# xhfc-breakout.net
KiCad netlist of a schematic drawn in EAGLE
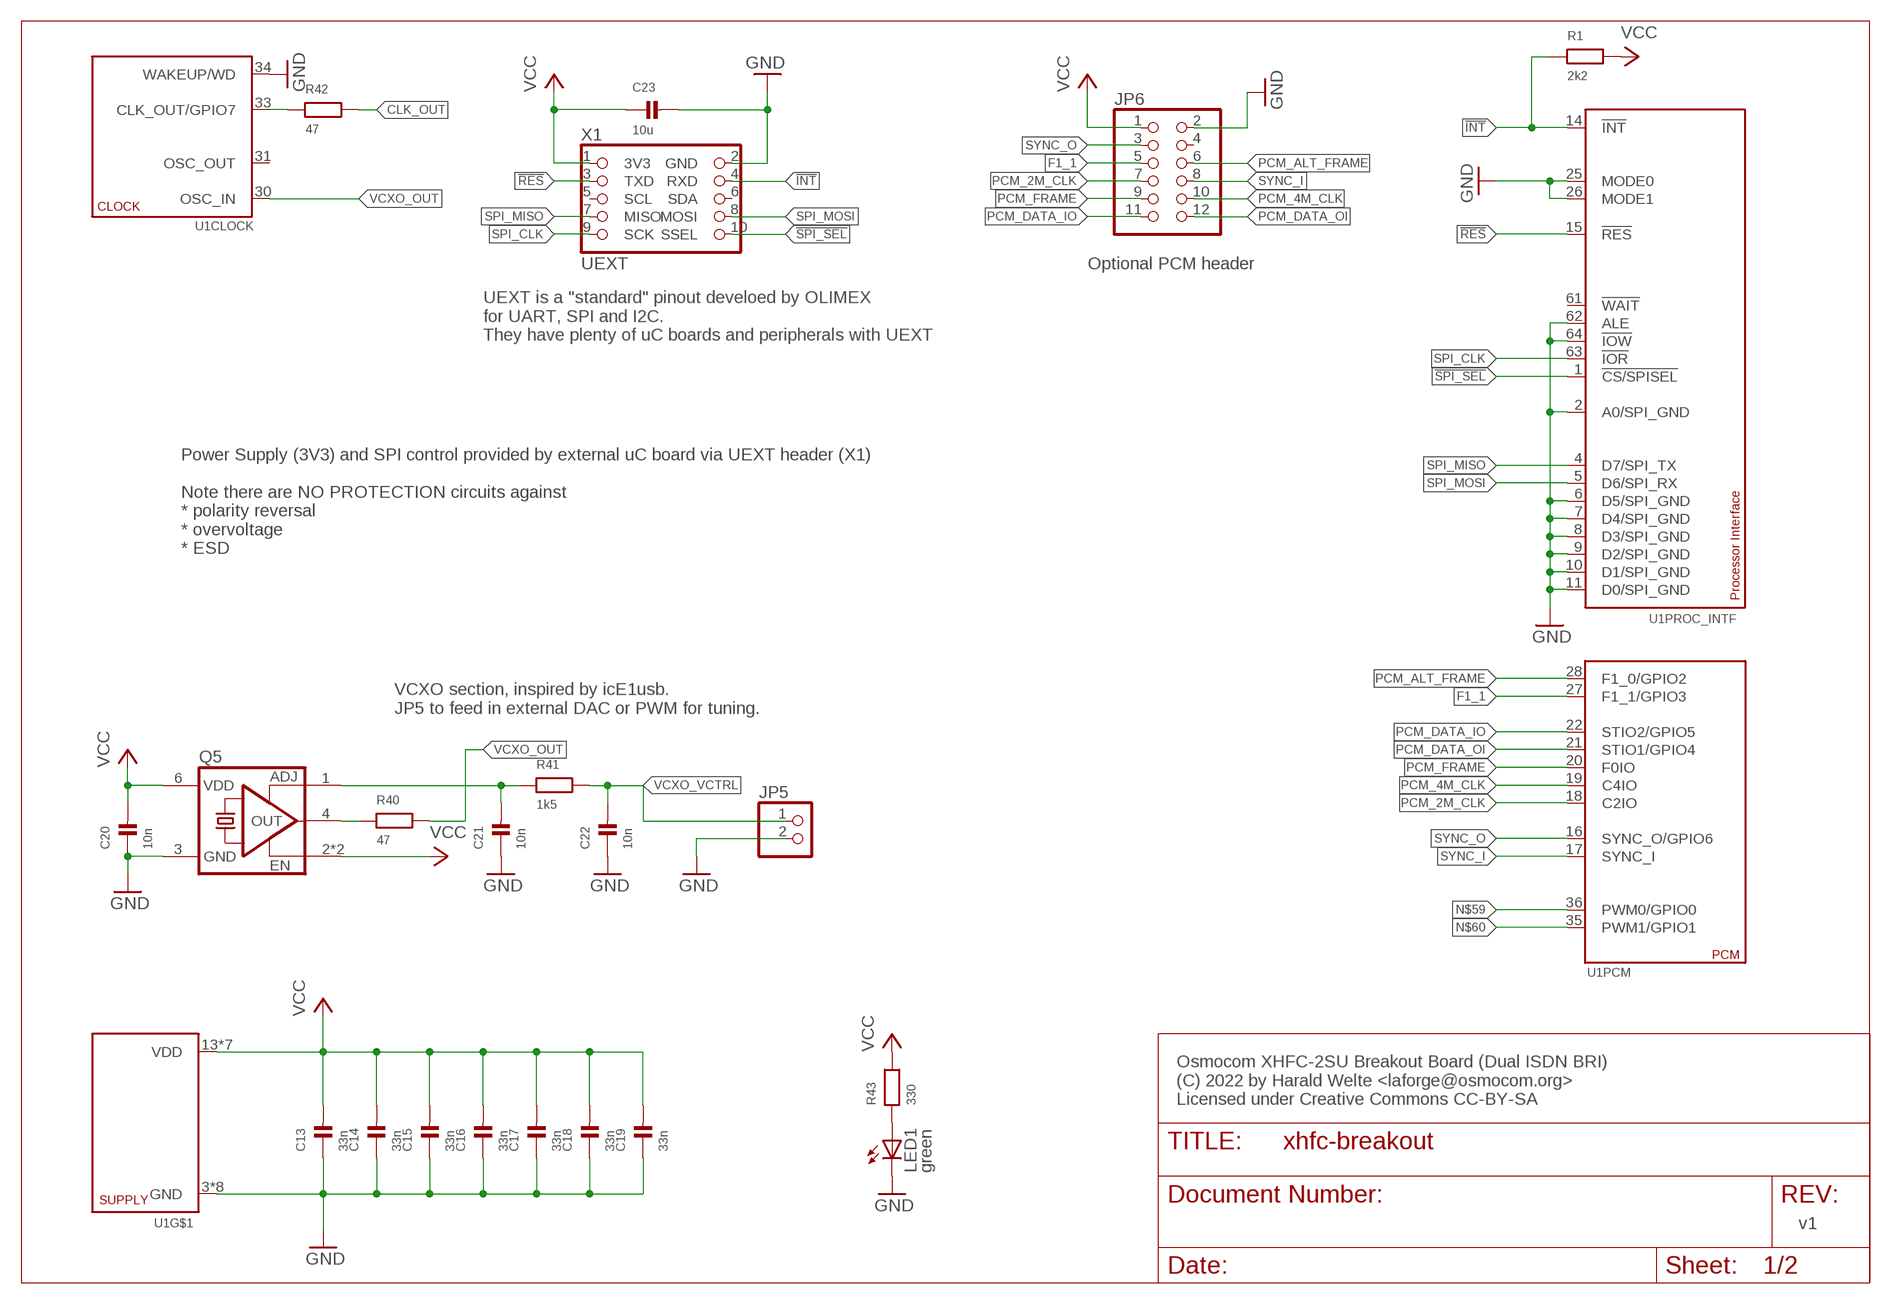
[diagram p0: schematic, sheet 1]
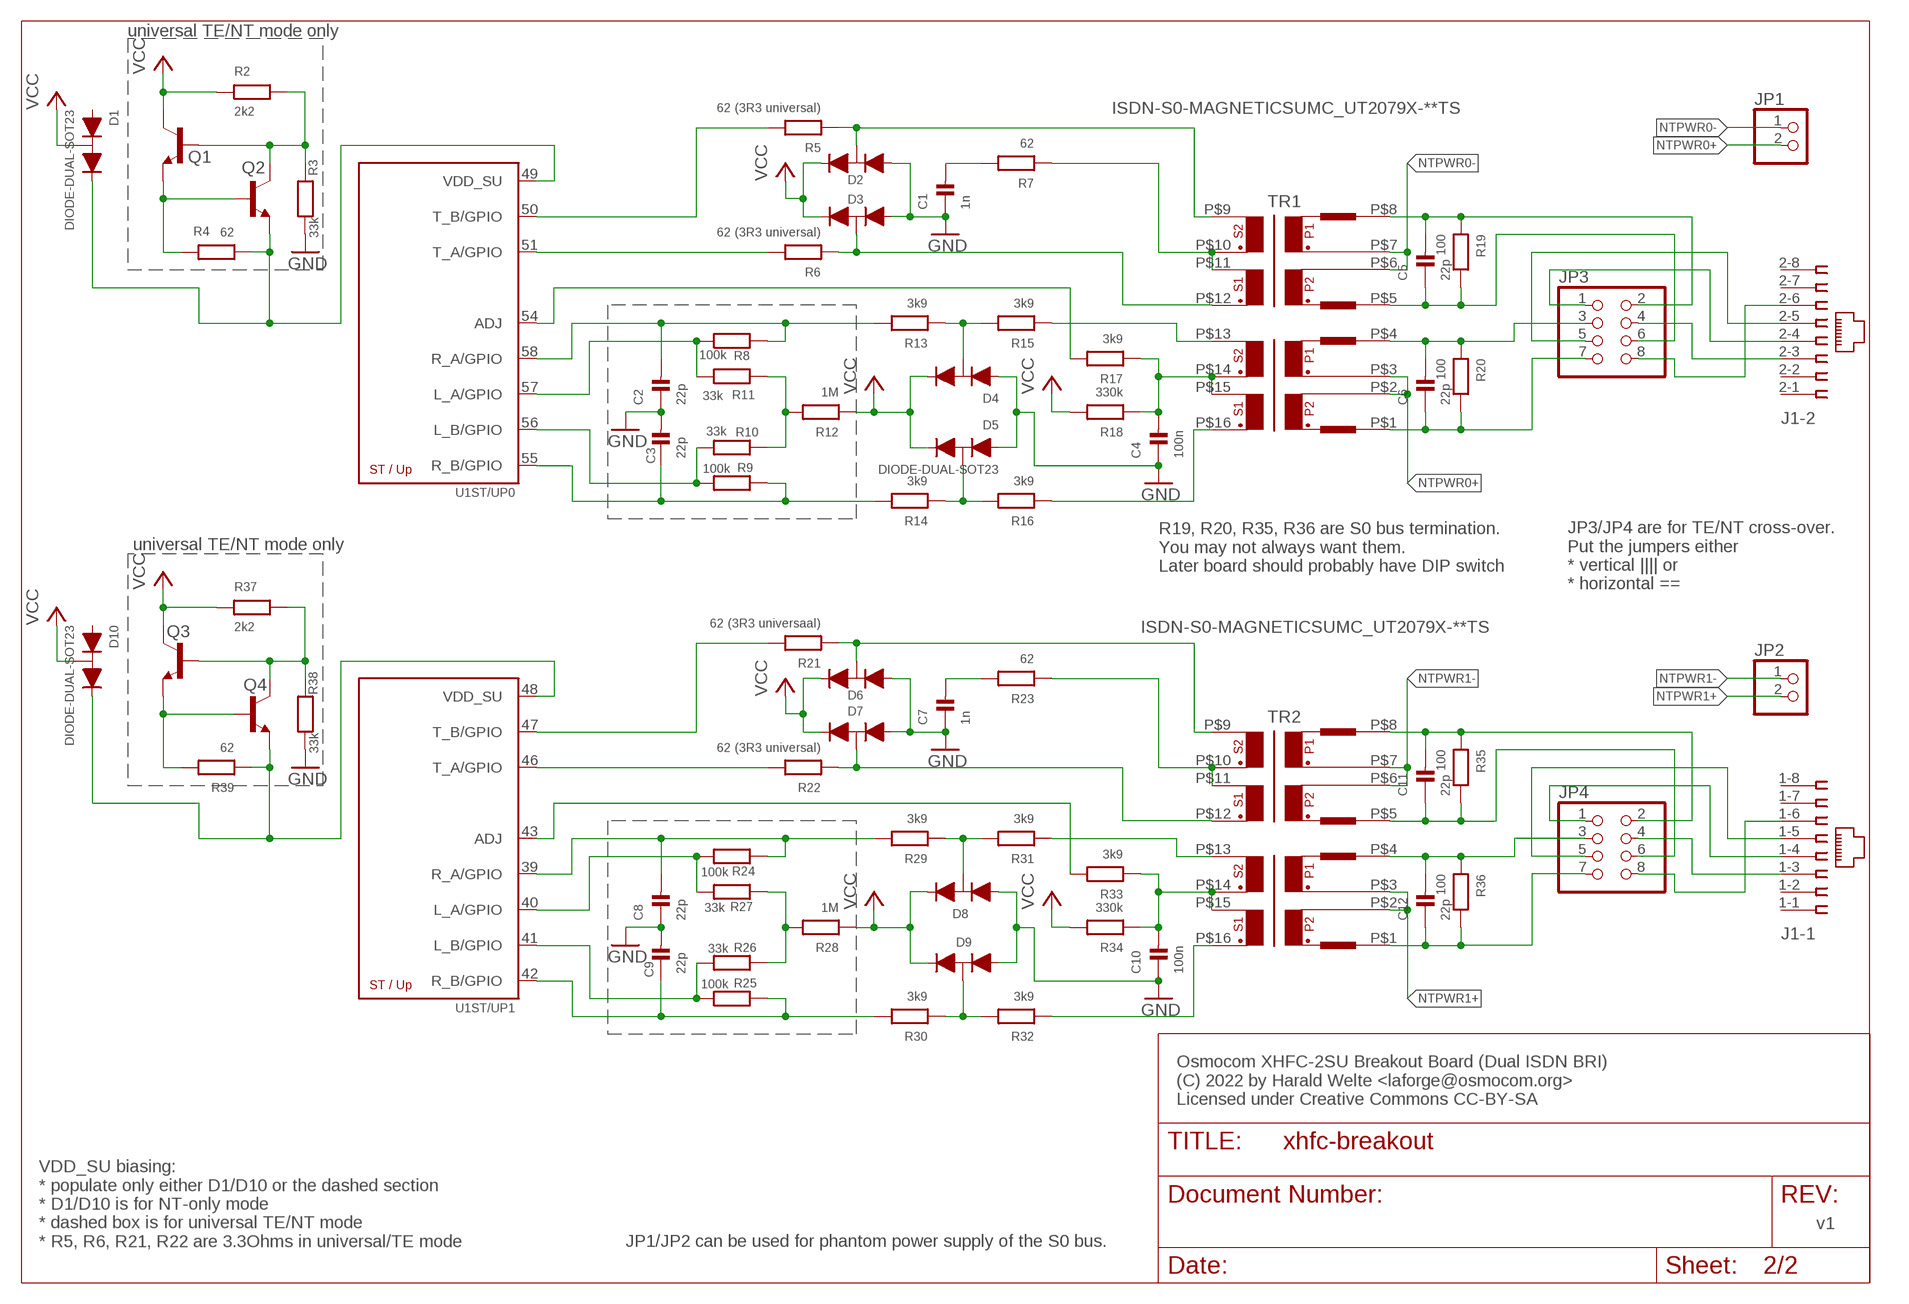
[diagram p1: schematic, sheet 2]

(export (version "E")
  (design (tool "Eeschema 10.0.6"))
  (components
    (comp (ref "C1")
      (value "1n")
      (footprint "eagle-import:_0603")
      (description "NO DESCRIPTION")
      (fields
        (field (name "MANUFACTURER") "UNKNOWN MANUFACTURER")
        (field (name "MANUFACTURERPARTNUMBER") "UNKNOWN MANUFACTURER PART NUMBER")
      )
      (libsource (lib "eagle-import") (part "CAP_CERAMIC_0603"))
    )
    (comp (ref "C2")
      (value "22p")
      (footprint "eagle-import:_0603")
      (description "NO DESCRIPTION")
      (fields
        (field (name "MANUFACTURER") "UNKNOWN MANUFACTURER")
        (field (name "MANUFACTURERPARTNUMBER") "UNKNOWN MANUFACTURER PART NUMBER")
      )
      (libsource (lib "eagle-import") (part "CAP_CERAMIC_0603"))
    )
    (comp (ref "C3")
      (value "22p")
      (footprint "eagle-import:_0603")
      (description "NO DESCRIPTION")
      (fields
        (field (name "MANUFACTURER") "UNKNOWN MANUFACTURER")
        (field (name "MANUFACTURERPARTNUMBER") "UNKNOWN MANUFACTURER PART NUMBER")
      )
      (libsource (lib "eagle-import") (part "CAP_CERAMIC_0603"))
    )
    (comp (ref "C4")
      (value "100n")
      (footprint "eagle-import:_0603")
      (description "NO DESCRIPTION")
      (fields
        (field (name "MANUFACTURER") "UNKNOWN MANUFACTURER")
        (field (name "MANUFACTURERPARTNUMBER") "UNKNOWN MANUFACTURER PART NUMBER")
      )
      (libsource (lib "eagle-import") (part "CAP_CERAMIC_0603"))
    )
    (comp (ref "C5")
      (value "22p")
      (footprint "eagle-import:_0603")
      (description "NO DESCRIPTION")
      (fields
        (field (name "MANUFACTURER") "UNKNOWN MANUFACTURER")
        (field (name "MANUFACTURERPARTNUMBER") "UNKNOWN MANUFACTURER PART NUMBER")
      )
      (libsource (lib "eagle-import") (part "CAP_CERAMIC_0603"))
    )
    (comp (ref "C6")
      (value "22p")
      (footprint "eagle-import:_0603")
      (description "NO DESCRIPTION")
      (fields
        (field (name "MANUFACTURER") "UNKNOWN MANUFACTURER")
        (field (name "MANUFACTURERPARTNUMBER") "UNKNOWN MANUFACTURER PART NUMBER")
      )
      (libsource (lib "eagle-import") (part "CAP_CERAMIC_0603"))
    )
    (comp (ref "C7")
      (value "1n")
      (footprint "eagle-import:_0603")
      (description "NO DESCRIPTION")
      (fields
        (field (name "MANUFACTURER") "UNKNOWN MANUFACTURER")
        (field (name "MANUFACTURERPARTNUMBER") "UNKNOWN MANUFACTURER PART NUMBER")
      )
      (libsource (lib "eagle-import") (part "CAP_CERAMIC_0603"))
    )
    (comp (ref "C8")
      (value "22p")
      (footprint "eagle-import:_0603")
      (description "NO DESCRIPTION")
      (fields
        (field (name "MANUFACTURER") "UNKNOWN MANUFACTURER")
        (field (name "MANUFACTURERPARTNUMBER") "UNKNOWN MANUFACTURER PART NUMBER")
      )
      (libsource (lib "eagle-import") (part "CAP_CERAMIC_0603"))
    )
    (comp (ref "C9")
      (value "22p")
      (footprint "eagle-import:_0603")
      (description "NO DESCRIPTION")
      (fields
        (field (name "MANUFACTURER") "UNKNOWN MANUFACTURER")
        (field (name "MANUFACTURERPARTNUMBER") "UNKNOWN MANUFACTURER PART NUMBER")
      )
      (libsource (lib "eagle-import") (part "CAP_CERAMIC_0603"))
    )
    (comp (ref "C10")
      (value "100n")
      (footprint "eagle-import:_0603")
      (description "NO DESCRIPTION")
      (fields
        (field (name "MANUFACTURER") "UNKNOWN MANUFACTURER")
        (field (name "MANUFACTURERPARTNUMBER") "UNKNOWN MANUFACTURER PART NUMBER")
      )
      (libsource (lib "eagle-import") (part "CAP_CERAMIC_0603"))
    )
    (comp (ref "C11")
      (value "22p")
      (footprint "eagle-import:_0603")
      (description "NO DESCRIPTION")
      (fields
        (field (name "MANUFACTURER") "UNKNOWN MANUFACTURER")
        (field (name "MANUFACTURERPARTNUMBER") "UNKNOWN MANUFACTURER PART NUMBER")
      )
      (libsource (lib "eagle-import") (part "CAP_CERAMIC_0603"))
    )
    (comp (ref "C12")
      (value "22p")
      (footprint "eagle-import:_0603")
      (description "NO DESCRIPTION")
      (fields
        (field (name "MANUFACTURER") "UNKNOWN MANUFACTURER")
        (field (name "MANUFACTURERPARTNUMBER") "UNKNOWN MANUFACTURER PART NUMBER")
      )
      (libsource (lib "eagle-import") (part "CAP_CERAMIC_0603"))
    )
    (comp (ref "D1")
      (value "DIODE-DUAL-SOT23")
      (footprint "eagle-import:SOT23-3")
      (description "DIODE ARRAY GP 100V 150MA SOT323")
      (fields
        (field (name "MANUFACTURER") "Nexperia USA Inc.")
        (field (name "MANUFACTURERPARTNUMBER") "BAV99W,115")
      )
      (libsource (lib "eagle-import") (part "DIODE-DUAL-SOT23"))
    )
    (comp (ref "D2")
      (value "DIODE-DUAL-SOT23")
      (footprint "eagle-import:SOT23-3")
      (description "DIODE ARRAY GP 100V 150MA SOT323")
      (fields
        (field (name "MANUFACTURER") "Nexperia USA Inc.")
        (field (name "MANUFACTURERPARTNUMBER") "BAV99W,115")
      )
      (libsource (lib "eagle-import") (part "DIODE-DUAL-SOT23"))
    )
    (comp (ref "D3")
      (value "DIODE-DUAL-SOT23")
      (footprint "eagle-import:SOT23-3")
      (description "DIODE ARRAY GP 100V 150MA SOT323")
      (fields
        (field (name "MANUFACTURER") "Nexperia USA Inc.")
        (field (name "MANUFACTURERPARTNUMBER") "BAV99W,115")
      )
      (libsource (lib "eagle-import") (part "DIODE-DUAL-SOT23"))
    )
    (comp (ref "D4")
      (value "DIODE-DUAL-SOT23")
      (footprint "eagle-import:SOT23-3")
      (description "DIODE ARRAY GP 100V 150MA SOT323")
      (fields
        (field (name "MANUFACTURER") "Nexperia USA Inc.")
        (field (name "MANUFACTURERPARTNUMBER") "BAV99W,115")
      )
      (libsource (lib "eagle-import") (part "DIODE-DUAL-SOT23"))
    )
    (comp (ref "D5")
      (value "DIODE-DUAL-SOT23")
      (footprint "eagle-import:SOT23-3")
      (description "DIODE ARRAY GP 100V 150MA SOT323")
      (fields
        (field (name "MANUFACTURER") "Nexperia USA Inc.")
        (field (name "MANUFACTURERPARTNUMBER") "BAV99W,115")
      )
      (libsource (lib "eagle-import") (part "DIODE-DUAL-SOT23"))
    )
    (comp (ref "D6")
      (value "DIODE-DUAL-SOT23")
      (footprint "eagle-import:SOT23-3")
      (description "DIODE ARRAY GP 100V 150MA SOT323")
      (fields
        (field (name "MANUFACTURER") "Nexperia USA Inc.")
        (field (name "MANUFACTURERPARTNUMBER") "BAV99W,115")
      )
      (libsource (lib "eagle-import") (part "DIODE-DUAL-SOT23"))
    )
    (comp (ref "D7")
      (value "DIODE-DUAL-SOT23")
      (footprint "eagle-import:SOT23-3")
      (description "DIODE ARRAY GP 100V 150MA SOT323")
      (fields
        (field (name "MANUFACTURER") "Nexperia USA Inc.")
        (field (name "MANUFACTURERPARTNUMBER") "BAV99W,115")
      )
      (libsource (lib "eagle-import") (part "DIODE-DUAL-SOT23"))
    )
    (comp (ref "D8")
      (value "DIODE-DUAL-SOT23")
      (footprint "eagle-import:SOT23-3")
      (description "DIODE ARRAY GP 100V 150MA SOT323")
      (fields
        (field (name "MANUFACTURER") "Nexperia USA Inc.")
        (field (name "MANUFACTURERPARTNUMBER") "BAV99W,115")
      )
      (libsource (lib "eagle-import") (part "DIODE-DUAL-SOT23"))
    )
    (comp (ref "D9")
      (value "DIODE-DUAL-SOT23")
      (footprint "eagle-import:SOT23-3")
      (description "DIODE ARRAY GP 100V 150MA SOT323")
      (fields
        (field (name "MANUFACTURER") "Nexperia USA Inc.")
        (field (name "MANUFACTURERPARTNUMBER") "BAV99W,115")
      )
      (libsource (lib "eagle-import") (part "DIODE-DUAL-SOT23"))
    )
    (comp (ref "D10")
      (value "DIODE-DUAL-SOT23")
      (footprint "eagle-import:SOT23-3")
      (description "DIODE ARRAY GP 100V 150MA SOT323")
      (fields
        (field (name "MANUFACTURER") "Nexperia USA Inc.")
        (field (name "MANUFACTURERPARTNUMBER") "BAV99W,115")
      )
      (libsource (lib "eagle-import") (part "DIODE-DUAL-SOT23"))
    )
    (comp (ref "J1")
      (value "557560-1")
      (footprint "eagle-import:557560-1")
      (description "CONN MOD JACK 8P8C R/A UNSHLD")
      (fields
        (field (name "MANUFACTURER") "TE Connectivity AMP Connectors")
        (field (name "MANUFACTURERPARTNUMBER") "5557560-1")
        (field (name "CLASS") "CONNECTOR\\JUMPER")
        (field (name "LINK") "https://www.digikey.com/en/products/detail/te-connectivity-amp-connectors/5557560-1/769593")
        (field (name "POPULATED") "TRUE")
        (field (name "ROHSCERTIFICATE") "RoHS Compliant")
        (field (name "SOURCE") "DIGIKEY")
        (field (name "SOURCEPARTNUMBER") "A31449-ND")
      )
      (libsource (lib "eagle-import") (part "557560-1"))
    )
    (comp (ref "JP1")
      (value "PINHD-1X2")
      (footprint "eagle-import:1X02")
      (description "NO DESCRIPTION")
      (fields
        (field (name "MANUFACTURER") "UNKNOWN MANUFACTURER")
        (field (name "MANUFACTURERPARTNUMBER") "UNKNOWN MANUFACTURER PART NUMBER")
      )
      (libsource (lib "eagle-import") (part "PINHD-1X2"))
    )
    (comp (ref "JP2")
      (value "PINHD-1X2")
      (footprint "eagle-import:1X02")
      (description "NO DESCRIPTION")
      (fields
        (field (name "MANUFACTURER") "UNKNOWN MANUFACTURER")
        (field (name "MANUFACTURERPARTNUMBER") "UNKNOWN MANUFACTURER PART NUMBER")
      )
      (libsource (lib "eagle-import") (part "PINHD-1X2"))
    )
    (comp (ref "JP3")
      (value "PINHD-2X4")
      (footprint "eagle-import:2X04")
      (description "NO DESCRIPTION")
      (fields
        (field (name "MANUFACTURER") "UNKNOWN MANUFACTURER")
        (field (name "MANUFACTURERPARTNUMBER") "UNKNOWN MANUFACTURER PART NUMBER")
      )
      (libsource (lib "eagle-import") (part "PINHD-2X4"))
    )
    (comp (ref "JP4")
      (value "PINHD-2X4")
      (footprint "eagle-import:2X04")
      (description "NO DESCRIPTION")
      (fields
        (field (name "MANUFACTURER") "UNKNOWN MANUFACTURER")
        (field (name "MANUFACTURERPARTNUMBER") "UNKNOWN MANUFACTURER PART NUMBER")
      )
      (libsource (lib "eagle-import") (part "PINHD-2X4"))
    )
    (comp (ref "Q1")
      (value "BC848CSMD")
      (footprint "eagle-import:SOT23")
      (description "TRANS NPN 30V 100MA SC70-3")
      (fields (field (name "MANUFACTURER") "onsemi") (field (name "MANUFACTURERPARTNUMBER") "BC848CWT1G"))
      (libsource (lib "eagle-import") (part "BC848SMDC"))
    )
    (comp (ref "Q2")
      (value "BC848CSMD")
      (footprint "eagle-import:SOT23")
      (description "TRANS NPN 30V 100MA SC70-3")
      (fields (field (name "MANUFACTURER") "onsemi") (field (name "MANUFACTURERPARTNUMBER") "BC848CWT1G"))
      (libsource (lib "eagle-import") (part "BC848SMDC"))
    )
    (comp (ref "Q3")
      (value "BC848CSMD")
      (footprint "eagle-import:SOT23")
      (description "TRANS NPN 30V 100MA SC70-3")
      (fields (field (name "MANUFACTURER") "onsemi") (field (name "MANUFACTURERPARTNUMBER") "BC848CWT1G"))
      (libsource (lib "eagle-import") (part "BC848SMDC"))
    )
    (comp (ref "Q4")
      (value "BC848CSMD")
      (footprint "eagle-import:SOT23")
      (description "TRANS NPN 30V 100MA SC70-3")
      (fields (field (name "MANUFACTURER") "onsemi") (field (name "MANUFACTURERPARTNUMBER") "BC848CWT1G"))
      (libsource (lib "eagle-import") (part "BC848SMDC"))
    )
    (comp (ref "R2")
      (value "2k2")
      (footprint "eagle-import:_0603")
      (description "NO DESCRIPTION")
      (fields
        (field (name "MANUFACTURER") "UNKNOWN MANUFACTURER")
        (field (name "MANUFACTURERPARTNUMBER") "UNKNOWN MANUFACTURER PART NUMBER")
      )
      (libsource (lib "eagle-import") (part "RESISTOR_0603"))
    )
    (comp (ref "R3")
      (value "33k")
      (footprint "eagle-import:_0603")
      (description "NO DESCRIPTION")
      (fields
        (field (name "MANUFACTURER") "UNKNOWN MANUFACTURER")
        (field (name "MANUFACTURERPARTNUMBER") "UNKNOWN MANUFACTURER PART NUMBER")
      )
      (libsource (lib "eagle-import") (part "RESISTOR_0603"))
    )
    (comp (ref "R4")
      (value "62")
      (footprint "eagle-import:_0603")
      (description "NO DESCRIPTION")
      (fields
        (field (name "MANUFACTURER") "UNKNOWN MANUFACTURER")
        (field (name "MANUFACTURERPARTNUMBER") "UNKNOWN MANUFACTURER PART NUMBER")
      )
      (libsource (lib "eagle-import") (part "RESISTOR_0603"))
    )
    (comp (ref "R5")
      (value "62 (3R3 universal)")
      (footprint "eagle-import:_0603")
      (description "NO DESCRIPTION")
      (fields
        (field (name "MANUFACTURER") "UNKNOWN MANUFACTURER")
        (field (name "MANUFACTURERPARTNUMBER") "UNKNOWN MANUFACTURER PART NUMBER")
      )
      (libsource (lib "eagle-import") (part "RESISTOR_0603"))
    )
    (comp (ref "R6")
      (value "62 (3R3 universal)")
      (footprint "eagle-import:_0603")
      (description "NO DESCRIPTION")
      (fields
        (field (name "MANUFACTURER") "UNKNOWN MANUFACTURER")
        (field (name "MANUFACTURERPARTNUMBER") "UNKNOWN MANUFACTURER PART NUMBER")
      )
      (libsource (lib "eagle-import") (part "RESISTOR_0603"))
    )
    (comp (ref "R7")
      (value "62")
      (footprint "eagle-import:_0603")
      (description "NO DESCRIPTION")
      (fields
        (field (name "MANUFACTURER") "UNKNOWN MANUFACTURER")
        (field (name "MANUFACTURERPARTNUMBER") "UNKNOWN MANUFACTURER PART NUMBER")
      )
      (libsource (lib "eagle-import") (part "RESISTOR_0603"))
    )
    (comp (ref "R8")
      (value "100k")
      (footprint "eagle-import:_0603")
      (description "NO DESCRIPTION")
      (fields
        (field (name "MANUFACTURER") "UNKNOWN MANUFACTURER")
        (field (name "MANUFACTURERPARTNUMBER") "UNKNOWN MANUFACTURER PART NUMBER")
      )
      (libsource (lib "eagle-import") (part "RESISTOR_0603"))
    )
    (comp (ref "R9")
      (value "100k")
      (footprint "eagle-import:_0603")
      (description "NO DESCRIPTION")
      (fields
        (field (name "MANUFACTURER") "UNKNOWN MANUFACTURER")
        (field (name "MANUFACTURERPARTNUMBER") "UNKNOWN MANUFACTURER PART NUMBER")
      )
      (libsource (lib "eagle-import") (part "RESISTOR_0603"))
    )
    (comp (ref "R10")
      (value "33k")
      (footprint "eagle-import:_0603")
      (description "NO DESCRIPTION")
      (fields
        (field (name "MANUFACTURER") "UNKNOWN MANUFACTURER")
        (field (name "MANUFACTURERPARTNUMBER") "UNKNOWN MANUFACTURER PART NUMBER")
      )
      (libsource (lib "eagle-import") (part "RESISTOR_0603"))
    )
    (comp (ref "R11")
      (value "33k")
      (footprint "eagle-import:_0603")
      (description "NO DESCRIPTION")
      (fields
        (field (name "MANUFACTURER") "UNKNOWN MANUFACTURER")
        (field (name "MANUFACTURERPARTNUMBER") "UNKNOWN MANUFACTURER PART NUMBER")
      )
      (libsource (lib "eagle-import") (part "RESISTOR_0603"))
    )
    (comp (ref "R12")
      (value "1M")
      (footprint "eagle-import:_0603")
      (description "NO DESCRIPTION")
      (fields
        (field (name "MANUFACTURER") "UNKNOWN MANUFACTURER")
        (field (name "MANUFACTURERPARTNUMBER") "UNKNOWN MANUFACTURER PART NUMBER")
      )
      (libsource (lib "eagle-import") (part "RESISTOR_0603"))
    )
    (comp (ref "R13")
      (value "3k9")
      (footprint "eagle-import:_0603")
      (description "NO DESCRIPTION")
      (fields
        (field (name "MANUFACTURER") "UNKNOWN MANUFACTURER")
        (field (name "MANUFACTURERPARTNUMBER") "UNKNOWN MANUFACTURER PART NUMBER")
      )
      (libsource (lib "eagle-import") (part "RESISTOR_0603"))
    )
    (comp (ref "R14")
      (value "3k9")
      (footprint "eagle-import:_0603")
      (description "NO DESCRIPTION")
      (fields
        (field (name "MANUFACTURER") "UNKNOWN MANUFACTURER")
        (field (name "MANUFACTURERPARTNUMBER") "UNKNOWN MANUFACTURER PART NUMBER")
      )
      (libsource (lib "eagle-import") (part "RESISTOR_0603"))
    )
    (comp (ref "R15")
      (value "3k9")
      (footprint "eagle-import:_0603")
      (description "NO DESCRIPTION")
      (fields
        (field (name "MANUFACTURER") "UNKNOWN MANUFACTURER")
        (field (name "MANUFACTURERPARTNUMBER") "UNKNOWN MANUFACTURER PART NUMBER")
      )
      (libsource (lib "eagle-import") (part "RESISTOR_0603"))
    )
    (comp (ref "R16")
      (value "3k9")
      (footprint "eagle-import:_0603")
      (description "NO DESCRIPTION")
      (fields
        (field (name "MANUFACTURER") "UNKNOWN MANUFACTURER")
        (field (name "MANUFACTURERPARTNUMBER") "UNKNOWN MANUFACTURER PART NUMBER")
      )
      (libsource (lib "eagle-import") (part "RESISTOR_0603"))
    )
    (comp (ref "R17")
      (value "3k9")
      (footprint "eagle-import:_0603")
      (description "NO DESCRIPTION")
      (fields
        (field (name "MANUFACTURER") "UNKNOWN MANUFACTURER")
        (field (name "MANUFACTURERPARTNUMBER") "UNKNOWN MANUFACTURER PART NUMBER")
      )
      (libsource (lib "eagle-import") (part "RESISTOR_0603"))
    )
    (comp (ref "R18")
      (value "330k")
      (footprint "eagle-import:_0603")
      (description "NO DESCRIPTION")
      (fields
        (field (name "MANUFACTURER") "UNKNOWN MANUFACTURER")
        (field (name "MANUFACTURERPARTNUMBER") "UNKNOWN MANUFACTURER PART NUMBER")
      )
      (libsource (lib "eagle-import") (part "RESISTOR_0603"))
    )
    (comp (ref "R19")
      (value "100")
      (footprint "eagle-import:_0603")
      (description "NO DESCRIPTION")
      (fields
        (field (name "MANUFACTURER") "UNKNOWN MANUFACTURER")
        (field (name "MANUFACTURERPARTNUMBER") "UNKNOWN MANUFACTURER PART NUMBER")
      )
      (libsource (lib "eagle-import") (part "RESISTOR_0603"))
    )
    (comp (ref "R20")
      (value "100")
      (footprint "eagle-import:_0603")
      (description "NO DESCRIPTION")
      (fields
        (field (name "MANUFACTURER") "UNKNOWN MANUFACTURER")
        (field (name "MANUFACTURERPARTNUMBER") "UNKNOWN MANUFACTURER PART NUMBER")
      )
      (libsource (lib "eagle-import") (part "RESISTOR_0603"))
    )
    (comp (ref "R21")
      (value "62 (3R3 universaal)")
      (footprint "eagle-import:_0603")
      (description "NO DESCRIPTION")
      (fields
        (field (name "MANUFACTURER") "UNKNOWN MANUFACTURER")
        (field (name "MANUFACTURERPARTNUMBER") "UNKNOWN MANUFACTURER PART NUMBER")
      )
      (libsource (lib "eagle-import") (part "RESISTOR_0603"))
    )
    (comp (ref "R22")
      (value "62 (3R3 universal)")
      (footprint "eagle-import:_0603")
      (description "NO DESCRIPTION")
      (fields
        (field (name "MANUFACTURER") "UNKNOWN MANUFACTURER")
        (field (name "MANUFACTURERPARTNUMBER") "UNKNOWN MANUFACTURER PART NUMBER")
      )
      (libsource (lib "eagle-import") (part "RESISTOR_0603"))
    )
    (comp (ref "R23")
      (value "62")
      (footprint "eagle-import:_0603")
      (description "NO DESCRIPTION")
      (fields
        (field (name "MANUFACTURER") "UNKNOWN MANUFACTURER")
        (field (name "MANUFACTURERPARTNUMBER") "UNKNOWN MANUFACTURER PART NUMBER")
      )
      (libsource (lib "eagle-import") (part "RESISTOR_0603"))
    )
    (comp (ref "R24")
      (value "100k")
      (footprint "eagle-import:_0603")
      (description "NO DESCRIPTION")
      (fields
        (field (name "MANUFACTURER") "UNKNOWN MANUFACTURER")
        (field (name "MANUFACTURERPARTNUMBER") "UNKNOWN MANUFACTURER PART NUMBER")
      )
      (libsource (lib "eagle-import") (part "RESISTOR_0603"))
    )
    (comp (ref "R25")
      (value "100k")
      (footprint "eagle-import:_0603")
      (description "NO DESCRIPTION")
      (fields
        (field (name "MANUFACTURER") "UNKNOWN MANUFACTURER")
        (field (name "MANUFACTURERPARTNUMBER") "UNKNOWN MANUFACTURER PART NUMBER")
      )
      (libsource (lib "eagle-import") (part "RESISTOR_0603"))
    )
    (comp (ref "R26")
      (value "33k")
      (footprint "eagle-import:_0603")
      (description "NO DESCRIPTION")
      (fields
        (field (name "MANUFACTURER") "UNKNOWN MANUFACTURER")
        (field (name "MANUFACTURERPARTNUMBER") "UNKNOWN MANUFACTURER PART NUMBER")
      )
      (libsource (lib "eagle-import") (part "RESISTOR_0603"))
    )
    (comp (ref "R27")
      (value "33k")
      (footprint "eagle-import:_0603")
      (description "NO DESCRIPTION")
      (fields
        (field (name "MANUFACTURER") "UNKNOWN MANUFACTURER")
        (field (name "MANUFACTURERPARTNUMBER") "UNKNOWN MANUFACTURER PART NUMBER")
      )
      (libsource (lib "eagle-import") (part "RESISTOR_0603"))
    )
    (comp (ref "R28")
      (value "1M")
      (footprint "eagle-import:_0603")
      (description "NO DESCRIPTION")
      (fields
        (field (name "MANUFACTURER") "UNKNOWN MANUFACTURER")
        (field (name "MANUFACTURERPARTNUMBER") "UNKNOWN MANUFACTURER PART NUMBER")
      )
      (libsource (lib "eagle-import") (part "RESISTOR_0603"))
    )
    (comp (ref "R29")
      (value "3k9")
      (footprint "eagle-import:_0603")
      (description "NO DESCRIPTION")
      (fields
        (field (name "MANUFACTURER") "UNKNOWN MANUFACTURER")
        (field (name "MANUFACTURERPARTNUMBER") "UNKNOWN MANUFACTURER PART NUMBER")
      )
      (libsource (lib "eagle-import") (part "RESISTOR_0603"))
    )
    (comp (ref "R30")
      (value "3k9")
      (footprint "eagle-import:_0603")
      (description "NO DESCRIPTION")
      (fields
        (field (name "MANUFACTURER") "UNKNOWN MANUFACTURER")
        (field (name "MANUFACTURERPARTNUMBER") "UNKNOWN MANUFACTURER PART NUMBER")
      )
      (libsource (lib "eagle-import") (part "RESISTOR_0603"))
    )
    (comp (ref "R31")
      (value "3k9")
      (footprint "eagle-import:_0603")
      (description "NO DESCRIPTION")
      (fields
        (field (name "MANUFACTURER") "UNKNOWN MANUFACTURER")
        (field (name "MANUFACTURERPARTNUMBER") "UNKNOWN MANUFACTURER PART NUMBER")
      )
      (libsource (lib "eagle-import") (part "RESISTOR_0603"))
    )
    (comp (ref "R32")
      (value "3k9")
      (footprint "eagle-import:_0603")
      (description "NO DESCRIPTION")
      (fields
        (field (name "MANUFACTURER") "UNKNOWN MANUFACTURER")
        (field (name "MANUFACTURERPARTNUMBER") "UNKNOWN MANUFACTURER PART NUMBER")
      )
      (libsource (lib "eagle-import") (part "RESISTOR_0603"))
    )
    (comp (ref "R33")
      (value "3k9")
      (footprint "eagle-import:_0603")
      (description "NO DESCRIPTION")
      (fields
        (field (name "MANUFACTURER") "UNKNOWN MANUFACTURER")
        (field (name "MANUFACTURERPARTNUMBER") "UNKNOWN MANUFACTURER PART NUMBER")
      )
      (libsource (lib "eagle-import") (part "RESISTOR_0603"))
    )
    (comp (ref "R34")
      (value "330k")
      (footprint "eagle-import:_0603")
      (description "NO DESCRIPTION")
      (fields
        (field (name "MANUFACTURER") "UNKNOWN MANUFACTURER")
        (field (name "MANUFACTURERPARTNUMBER") "UNKNOWN MANUFACTURER PART NUMBER")
      )
      (libsource (lib "eagle-import") (part "RESISTOR_0603"))
    )
    (comp (ref "R35")
      (value "100")
      (footprint "eagle-import:_0603")
      (description "NO DESCRIPTION")
      (fields
        (field (name "MANUFACTURER") "UNKNOWN MANUFACTURER")
        (field (name "MANUFACTURERPARTNUMBER") "UNKNOWN MANUFACTURER PART NUMBER")
      )
      (libsource (lib "eagle-import") (part "RESISTOR_0603"))
    )
    (comp (ref "R36")
      (value "100")
      (footprint "eagle-import:_0603")
      (description "NO DESCRIPTION")
      (fields
        (field (name "MANUFACTURER") "UNKNOWN MANUFACTURER")
        (field (name "MANUFACTURERPARTNUMBER") "UNKNOWN MANUFACTURER PART NUMBER")
      )
      (libsource (lib "eagle-import") (part "RESISTOR_0603"))
    )
    (comp (ref "R37")
      (value "2k2")
      (footprint "eagle-import:_0603")
      (description "NO DESCRIPTION")
      (fields
        (field (name "MANUFACTURER") "UNKNOWN MANUFACTURER")
        (field (name "MANUFACTURERPARTNUMBER") "UNKNOWN MANUFACTURER PART NUMBER")
      )
      (libsource (lib "eagle-import") (part "RESISTOR_0603"))
    )
    (comp (ref "R38")
      (value "33k")
      (footprint "eagle-import:_0603")
      (description "NO DESCRIPTION")
      (fields
        (field (name "MANUFACTURER") "UNKNOWN MANUFACTURER")
        (field (name "MANUFACTURERPARTNUMBER") "UNKNOWN MANUFACTURER PART NUMBER")
      )
      (libsource (lib "eagle-import") (part "RESISTOR_0603"))
    )
    (comp (ref "R39")
      (value "62")
      (footprint "eagle-import:_0603")
      (description "NO DESCRIPTION")
      (fields
        (field (name "MANUFACTURER") "UNKNOWN MANUFACTURER")
        (field (name "MANUFACTURERPARTNUMBER") "UNKNOWN MANUFACTURER PART NUMBER")
      )
      (libsource (lib "eagle-import") (part "RESISTOR_0603"))
    )
    (comp (ref "TR1")
      (value "ISDN-S0-MAGNETICSUMC_UT2079X-**TS")
      (footprint "eagle-import:UMEC_UT207")
      (description "NO DESCRIPTION")
      (fields (field (name "MANUFACTURER") "UMEC") (field (name "MANUFACTURERPARTNUMBER") "UT20795-5MTS"))
      (libsource (lib "eagle-import") (part "ISDN-S0-MAGNETICSUMC_UT2079X-TS"))
    )
    (comp (ref "TR2")
      (value "ISDN-S0-MAGNETICSUMC_UT2079X-**TS")
      (footprint "eagle-import:UMEC_UT207")
      (description "NO DESCRIPTION")
      (fields (field (name "MANUFACTURER") "UMEC") (field (name "MANUFACTURERPARTNUMBER") "UT20795-5MTS"))
      (libsource (lib "eagle-import") (part "ISDN-S0-MAGNETICSUMC_UT2079X-TS"))
    )
    (comp (ref "U1")
      (value "XHFC-2SU")
      (footprint "eagle-import:LQFP64")
      (description "NO DESCRIPTION")
      (fields
        (field (name "CLASS") "IC")
        (field (name "LINK") "UNKNOWN LINK")
        (field (name "MANUFACTURER") "UNKNOWN MANUFACTURER")
        (field (name "MANUFACTURERPARTNUMBER") "XHFC-2SU")
        (field (name "POPULATED") "TRUE")
        (field (name "ROHSCERTIFICATE") "UNKNOWN ROHS CERTIFICATE")
        (field (name "SOURCE") "CologneChip")
        (field (name "SOURCEPARTNUMBER") "UNKNOWN SOURCE PART NUMBER")
      )
      (libsource (lib "eagle-import") (part "XHFC-2SU"))
    )
    (comp (ref "C13")
      (value "33n")
      (footprint "eagle-import:_0603")
      (description "NO DESCRIPTION")
      (fields
        (field (name "MANUFACTURER") "UNKNOWN MANUFACTURER")
        (field (name "MANUFACTURERPARTNUMBER") "UNKNOWN MANUFACTURER PART NUMBER")
      )
      (libsource (lib "eagle-import") (part "CAP_CERAMIC_0603"))
    )
    (comp (ref "C14")
      (value "33n")
      (footprint "eagle-import:_0603")
      (description "NO DESCRIPTION")
      (fields
        (field (name "MANUFACTURER") "UNKNOWN MANUFACTURER")
        (field (name "MANUFACTURERPARTNUMBER") "UNKNOWN MANUFACTURER PART NUMBER")
      )
      (libsource (lib "eagle-import") (part "CAP_CERAMIC_0603"))
    )
    (comp (ref "C15")
      (value "33n")
      (footprint "eagle-import:_0603")
      (description "NO DESCRIPTION")
      (fields
        (field (name "MANUFACTURER") "UNKNOWN MANUFACTURER")
        (field (name "MANUFACTURERPARTNUMBER") "UNKNOWN MANUFACTURER PART NUMBER")
      )
      (libsource (lib "eagle-import") (part "CAP_CERAMIC_0603"))
    )
    (comp (ref "C16")
      (value "33n")
      (footprint "eagle-import:_0603")
      (description "NO DESCRIPTION")
      (fields
        (field (name "MANUFACTURER") "UNKNOWN MANUFACTURER")
        (field (name "MANUFACTURERPARTNUMBER") "UNKNOWN MANUFACTURER PART NUMBER")
      )
      (libsource (lib "eagle-import") (part "CAP_CERAMIC_0603"))
    )
    (comp (ref "C17")
      (value "33n")
      (footprint "eagle-import:_0603")
      (description "NO DESCRIPTION")
      (fields
        (field (name "MANUFACTURER") "UNKNOWN MANUFACTURER")
        (field (name "MANUFACTURERPARTNUMBER") "UNKNOWN MANUFACTURER PART NUMBER")
      )
      (libsource (lib "eagle-import") (part "CAP_CERAMIC_0603"))
    )
    (comp (ref "C18")
      (value "33n")
      (footprint "eagle-import:_0603")
      (description "NO DESCRIPTION")
      (fields
        (field (name "MANUFACTURER") "UNKNOWN MANUFACTURER")
        (field (name "MANUFACTURERPARTNUMBER") "UNKNOWN MANUFACTURER PART NUMBER")
      )
      (libsource (lib "eagle-import") (part "CAP_CERAMIC_0603"))
    )
    (comp (ref "C19")
      (value "33n")
      (footprint "eagle-import:_0603")
      (description "NO DESCRIPTION")
      (fields
        (field (name "MANUFACTURER") "UNKNOWN MANUFACTURER")
        (field (name "MANUFACTURERPARTNUMBER") "UNKNOWN MANUFACTURER PART NUMBER")
      )
      (libsource (lib "eagle-import") (part "CAP_CERAMIC_0603"))
    )
    (comp (ref "C20")
      (value "10n")
      (footprint "eagle-import:_0603")
      (description "NO DESCRIPTION")
      (fields
        (field (name "MANUFACTURER") "UNKNOWN MANUFACTURER")
        (field (name "MANUFACTURERPARTNUMBER") "UNKNOWN MANUFACTURER PART NUMBER")
      )
      (libsource (lib "eagle-import") (part "CAP_CERAMIC_0603"))
    )
    (comp (ref "C21")
      (value "10n")
      (footprint "eagle-import:_0603")
      (description "NO DESCRIPTION")
      (fields
        (field (name "MANUFACTURER") "UNKNOWN MANUFACTURER")
        (field (name "MANUFACTURERPARTNUMBER") "UNKNOWN MANUFACTURER PART NUMBER")
      )
      (libsource (lib "eagle-import") (part "CAP_CERAMIC_0603"))
    )
    (comp (ref "C22")
      (value "10n")
      (footprint "eagle-import:_0603")
      (description "NO DESCRIPTION")
      (fields
        (field (name "MANUFACTURER") "UNKNOWN MANUFACTURER")
        (field (name "MANUFACTURERPARTNUMBER") "UNKNOWN MANUFACTURER PART NUMBER")
      )
      (libsource (lib "eagle-import") (part "CAP_CERAMIC_0603"))
    )
    (comp (ref "C23")
      (value "10u")
      (footprint "eagle-import:1206")
      (description "NO DESCRIPTION")
      (fields
        (field (name "MANUFACTURER") "UNKNOWN MANUFACTURER")
        (field (name "MANUFACTURERPARTNUMBER") "UNKNOWN MANUFACTURER PART NUMBER")
      )
      (libsource (lib "eagle-import") (part "CAP_CERAMIC1206"))
    )
    (comp (ref "JP5")
      (value "PINHD-1X2")
      (footprint "eagle-import:1X02")
      (description "NO DESCRIPTION")
      (fields
        (field (name "MANUFACTURER") "UNKNOWN MANUFACTURER")
        (field (name "MANUFACTURERPARTNUMBER") "UNKNOWN MANUFACTURER PART NUMBER")
      )
      (libsource (lib "eagle-import") (part "PINHD-1X2"))
    )
    (comp (ref "JP6")
      (value "PINHD-2X6")
      (footprint "eagle-import:2X06")
      (description "NO DESCRIPTION")
      (fields
        (field (name "MANUFACTURER") "UNKNOWN MANUFACTURER")
        (field (name "MANUFACTURERPARTNUMBER") "UNKNOWN MANUFACTURER PART NUMBER")
      )
      (libsource (lib "eagle-import") (part "PINHD-2X6"))
    )
    (comp (ref "LED1")
      (value "green")
      (footprint "eagle-import:CHIP-LED0603")
      (description "NO DESCRIPTION")
      (fields
        (field (name "MANUFACTURER") "UNKNOWN MANUFACTURER")
        (field (name "MANUFACTURERPARTNUMBER") "UNKNOWN MANUFACTURER PART NUMBER")
      )
      (libsource (lib "eagle-import") (part "LEDCHIP-LED0603"))
    )
    (comp (ref "Q5")
      (value "VCXO-EN-VKB")
      (footprint "eagle-import:VKB")
      (description "XTAL OSC VCXO 24.5760MHZ LVCMOS")
      (fields
        (field (name "MANUFACTURER") "Connor Winfield")
        (field (name "MANUFACTURERPARTNUMBER") "VKB51B2-024.576M")
      )
      (libsource (lib "eagle-import") (part "VCXO-EN-VKB"))
    )
    (comp (ref "R1")
      (value "2k2")
      (footprint "eagle-import:_0603")
      (description "NO DESCRIPTION")
      (fields
        (field (name "MANUFACTURER") "UNKNOWN MANUFACTURER")
        (field (name "MANUFACTURERPARTNUMBER") "UNKNOWN MANUFACTURER PART NUMBER")
      )
      (libsource (lib "eagle-import") (part "RESISTOR_0603"))
    )
    (comp (ref "R40")
      (value "47")
      (footprint "eagle-import:_0603")
      (description "NO DESCRIPTION")
      (fields
        (field (name "MANUFACTURER") "UNKNOWN MANUFACTURER")
        (field (name "MANUFACTURERPARTNUMBER") "UNKNOWN MANUFACTURER PART NUMBER")
      )
      (libsource (lib "eagle-import") (part "RESISTOR_0603"))
    )
    (comp (ref "R41")
      (value "1k5")
      (footprint "eagle-import:_0603")
      (description "NO DESCRIPTION")
      (fields
        (field (name "MANUFACTURER") "UNKNOWN MANUFACTURER")
        (field (name "MANUFACTURERPARTNUMBER") "UNKNOWN MANUFACTURER PART NUMBER")
      )
      (libsource (lib "eagle-import") (part "RESISTOR_0603"))
    )
    (comp (ref "R42")
      (value "47")
      (footprint "eagle-import:_0603")
      (description "NO DESCRIPTION")
      (fields
        (field (name "MANUFACTURER") "UNKNOWN MANUFACTURER")
        (field (name "MANUFACTURERPARTNUMBER") "UNKNOWN MANUFACTURER PART NUMBER")
      )
      (libsource (lib "eagle-import") (part "RESISTOR_0603"))
    )
    (comp (ref "R43")
      (value "330")
      (footprint "eagle-import:_0603")
      (description "NO DESCRIPTION")
      (fields
        (field (name "MANUFACTURER") "UNKNOWN MANUFACTURER")
        (field (name "MANUFACTURERPARTNUMBER") "UNKNOWN MANUFACTURER PART NUMBER")
      )
      (libsource (lib "eagle-import") (part "RESISTOR_0603"))
    )
    (comp (ref "X1")
      (value "UEXT")
      (footprint "eagle-import:2X05")
      (description "NO DESCRIPTION")
      (fields
        (field (name "MANUFACTURER") "UNKNOWN MANUFACTURER")
        (field (name "MANUFACTURERPARTNUMBER") "UNKNOWN MANUFACTURER PART NUMBER")
      )
      (libsource (lib "eagle-import") (part "UEXT"))
    )
  )
  (nets
    (net (code "1") (name "CLK_OUT") (class "Default")
      (node (ref "R42") (pin "2") (pinfunction "2_2") (pintype "passive"))
    )
    (net (code "2") (name "F1_1") (class "Default")
      (node (ref "JP6") (pin "5") (pinfunction "5_5") (pintype "passive"))
      (node (ref "U1") (pin "27") (pinfunction "F1_1/GPIO3_27") (pintype "bidirectional"))
    )
    (net (code "3") (name "GND") (class "Default")
      (node (ref "C1") (pin "1") (pinfunction "1_1") (pintype "passive"))
      (node (ref "C10") (pin "1") (pinfunction "1_1") (pintype "passive"))
      (node (ref "C13") (pin "1") (pinfunction "1_1") (pintype "passive"))
      (node (ref "C14") (pin "1") (pinfunction "1_1") (pintype "passive"))
      (node (ref "C15") (pin "1") (pinfunction "1_1") (pintype "passive"))
      (node (ref "C16") (pin "1") (pinfunction "1_1") (pintype "passive"))
      (node (ref "C17") (pin "1") (pinfunction "1_1") (pintype "passive"))
      (node (ref "C18") (pin "1") (pinfunction "1_1") (pintype "passive"))
      (node (ref "C19") (pin "1") (pinfunction "1_1") (pintype "passive"))
      (node (ref "C2") (pin "1") (pinfunction "1_1") (pintype "passive"))
      (node (ref "C20") (pin "1") (pinfunction "1_1") (pintype "passive"))
      (node (ref "C21") (pin "1") (pinfunction "1_1") (pintype "passive"))
      (node (ref "C22") (pin "1") (pinfunction "1_1") (pintype "passive"))
      (node (ref "C23") (pin "2") (pinfunction "2_2") (pintype "passive"))
      (node (ref "C3") (pin "2") (pinfunction "2_2") (pintype "passive"))
      (node (ref "C4") (pin "1") (pinfunction "1_1") (pintype "passive"))
      (node (ref "C7") (pin "1") (pinfunction "1_1") (pintype "passive"))
      (node (ref "C8") (pin "1") (pinfunction "1_1") (pintype "passive"))
      (node (ref "C9") (pin "2") (pinfunction "2_2") (pintype "passive"))
      (node (ref "D2") (pin "1") (pinfunction "A_1") (pintype "passive"))
      (node (ref "D3") (pin "1") (pinfunction "A_1") (pintype "passive"))
      (node (ref "D4") (pin "1") (pinfunction "A_1") (pintype "passive"))
      (node (ref "D5") (pin "1") (pinfunction "A_1") (pintype "passive"))
      (node (ref "D6") (pin "1") (pinfunction "A_1") (pintype "passive"))
      (node (ref "D7") (pin "1") (pinfunction "A_1") (pintype "passive"))
      (node (ref "D8") (pin "1") (pinfunction "A_1") (pintype "passive"))
      (node (ref "D9") (pin "1") (pinfunction "A_1") (pintype "passive"))
      (node (ref "JP5") (pin "2") (pinfunction "2_2") (pintype "passive"))
      (node (ref "JP6") (pin "2") (pinfunction "2_2") (pintype "passive"))
      (node (ref "LED1") (pin "C") (pinfunction "C_C") (pintype "passive"))
      (node (ref "Q5") (pin "3") (pinfunction "GND_3") (pintype "power_in"))
      (node (ref "R3") (pin "1") (pinfunction "1_1") (pintype "passive"))
      (node (ref "R38") (pin "1") (pinfunction "1_1") (pintype "passive"))
      (node (ref "U1") (pin "10") (pinfunction "D1/SPI_GND_10") (pintype "bidirectional"))
      (node (ref "U1") (pin "11") (pinfunction "D0/SPI_GND_11") (pintype "bidirectional"))
      (node (ref "U1") (pin "12") (pinfunction "GND_12") (pintype "passive"))
      (node (ref "U1") (pin "2") (pinfunction "A0/SPI_GND_2") (pintype "input"))
      (node (ref "U1") (pin "23") (pinfunction "GND_23") (pintype "passive"))
      (node (ref "U1") (pin "25") (pinfunction "MODE0_25") (pintype "input"))
      (node (ref "U1") (pin "26") (pinfunction "MODE1_26") (pintype "input"))
      (node (ref "U1") (pin "3") (pinfunction "GND_3") (pintype "passive"))
      (node (ref "U1") (pin "32") (pinfunction "GND_32") (pintype "passive"))
      (node (ref "U1") (pin "34") (pinfunction "WAKEUP/WD_34") (pintype "bidirectional"))
      (node (ref "U1") (pin "38") (pinfunction "GND_38") (pintype "passive"))
      (node (ref "U1") (pin "45") (pinfunction "GND_45") (pintype "passive"))
      (node (ref "U1") (pin "52") (pinfunction "GND_52") (pintype "passive"))
      (node (ref "U1") (pin "59") (pinfunction "GND_59") (pintype "passive"))
      (node (ref "U1") (pin "6") (pinfunction "D5/SPI_GND_6") (pintype "bidirectional"))
      (node (ref "U1") (pin "62") (pinfunction "ALE_62") (pintype "input"))
      (node (ref "U1") (pin "64") (pinfunction "~{IOW}_64") (pintype "input"))
      (node (ref "U1") (pin "7") (pinfunction "D4/SPI_GND_7") (pintype "bidirectional"))
      (node (ref "U1") (pin "8") (pinfunction "D3/SPI_GND_8") (pintype "bidirectional"))
      (node (ref "U1") (pin "9") (pinfunction "D2/SPI_GND_9") (pintype "bidirectional"))
      (node (ref "X1") (pin "2") (pinfunction "GND_2") (pintype "passive"))
    )
    (net (code "4") (name "N$59") (class "Default")
      (node (ref "U1") (pin "36") (pinfunction "PWM0/GPIO0_36") (pintype "bidirectional"))
    )
    (net (code "5") (name "N$60") (class "Default")
      (node (ref "U1") (pin "35") (pinfunction "PWM1/GPIO1_35") (pintype "bidirectional"))
    )
    (net (code "6") (name "NTPWR0+") (class "Default")
      (node (ref "JP1") (pin "2") (pinfunction "2_2") (pintype "passive"))
      (node (ref "TR1") (pin "P$2") (pinfunction "2_P$2") (pintype "passive"))
      (node (ref "TR1") (pin "P$3") (pinfunction "3_P$3") (pintype "passive"))
    )
    (net (code "7") (name "NTPWR0-") (class "Default")
      (node (ref "JP1") (pin "1") (pinfunction "1_1") (pintype "passive"))
      (node (ref "TR1") (pin "P$6") (pinfunction "6_P$6") (pintype "passive"))
      (node (ref "TR1") (pin "P$7") (pinfunction "7_P$7") (pintype "passive"))
    )
    (net (code "8") (name "NTPWR1+") (class "Default")
      (node (ref "JP2") (pin "2") (pinfunction "2_2") (pintype "passive"))
      (node (ref "TR2") (pin "P$2") (pinfunction "2_P$2") (pintype "passive"))
      (node (ref "TR2") (pin "P$3") (pinfunction "3_P$3") (pintype "passive"))
    )
    (net (code "9") (name "NTPWR1-") (class "Default")
      (node (ref "JP2") (pin "1") (pinfunction "1_1") (pintype "passive"))
      (node (ref "TR2") (pin "P$6") (pinfunction "6_P$6") (pintype "passive"))
      (node (ref "TR2") (pin "P$7") (pinfunction "7_P$7") (pintype "passive"))
    )
    (net (code "10") (name "Net-(C1-Pad2)") (class "Default")
      (node (ref "C1") (pin "2") (pinfunction "2_2") (pintype "passive"))
      (node (ref "R7") (pin "2") (pinfunction "2_2") (pintype "passive"))
    )
    (net (code "11") (name "Net-(C7-Pad2)") (class "Default")
      (node (ref "C7") (pin "2") (pinfunction "2_2") (pintype "passive"))
      (node (ref "R23") (pin "2") (pinfunction "2_2") (pintype "passive"))
    )
    (net (code "12") (name "Net-(D1-C)") (class "Default")
      (node (ref "D1") (pin "2") (pinfunction "C_2") (pintype "passive"))
      (node (ref "Q2") (pin "2") (pinfunction "E_2") (pintype "passive"))
      (node (ref "R4") (pin "1") (pinfunction "1_1") (pintype "passive"))
      (node (ref "U1") (pin "49") (pinfunction "VDD_SU_49") (pintype "bidirectional"))
    )
    (net (code "13") (name "Net-(D2-M)") (class "Default")
      (node (ref "D2") (pin "3") (pinfunction "M_3") (pintype "passive"))
      (node (ref "R5") (pin "1") (pinfunction "1_1") (pintype "passive"))
      (node (ref "TR1") (pin "P$9") (pinfunction "9_P$9") (pintype "passive"))
    )
    (net (code "14") (name "Net-(D3-M)") (class "Default")
      (node (ref "D3") (pin "3") (pinfunction "M_3") (pintype "passive"))
      (node (ref "R6") (pin "1") (pinfunction "1_1") (pintype "passive"))
      (node (ref "TR1") (pin "P$12") (pinfunction "12_P$12") (pintype "passive"))
    )
    (net (code "15") (name "Net-(D4-M)") (class "Default")
      (node (ref "D4") (pin "3") (pinfunction "M_3") (pintype "passive"))
      (node (ref "R13") (pin "1") (pinfunction "1_1") (pintype "passive"))
      (node (ref "R15") (pin "2") (pinfunction "2_2") (pintype "passive"))
    )
    (net (code "16") (name "Net-(D5-M)") (class "Default")
      (node (ref "D5") (pin "3") (pinfunction "M_3") (pintype "passive"))
      (node (ref "R14") (pin "1") (pinfunction "1_1") (pintype "passive"))
      (node (ref "R16") (pin "2") (pinfunction "2_2") (pintype "passive"))
    )
    (net (code "17") (name "Net-(D6-M)") (class "Default")
      (node (ref "D6") (pin "3") (pinfunction "M_3") (pintype "passive"))
      (node (ref "R21") (pin "1") (pinfunction "1_1") (pintype "passive"))
      (node (ref "TR2") (pin "P$9") (pinfunction "9_P$9") (pintype "passive"))
    )
    (net (code "18") (name "Net-(D7-M)") (class "Default")
      (node (ref "D7") (pin "3") (pinfunction "M_3") (pintype "passive"))
      (node (ref "R22") (pin "1") (pinfunction "1_1") (pintype "passive"))
      (node (ref "TR2") (pin "P$12") (pinfunction "12_P$12") (pintype "passive"))
    )
    (net (code "19") (name "Net-(D8-M)") (class "Default")
      (node (ref "D8") (pin "3") (pinfunction "M_3") (pintype "passive"))
      (node (ref "R29") (pin "1") (pinfunction "1_1") (pintype "passive"))
      (node (ref "R31") (pin "2") (pinfunction "2_2") (pintype "passive"))
    )
    (net (code "20") (name "Net-(D9-M)") (class "Default")
      (node (ref "D9") (pin "3") (pinfunction "M_3") (pintype "passive"))
      (node (ref "R30") (pin "1") (pinfunction "1_1") (pintype "passive"))
      (node (ref "R32") (pin "2") (pinfunction "2_2") (pintype "passive"))
    )
    (net (code "21") (name "Net-(D10-C)") (class "Default")
      (node (ref "D10") (pin "2") (pinfunction "C_2") (pintype "passive"))
      (node (ref "Q4") (pin "2") (pinfunction "E_2") (pintype "passive"))
      (node (ref "R39") (pin "1") (pinfunction "1_1") (pintype "passive"))
      (node (ref "U1") (pin "48") (pinfunction "VDD_SU_48") (pintype "bidirectional"))
    )
    (net (code "22") (name "Net-(J1A-3)") (class "Default")
      (node (ref "J1") (pin "1-3") (pinfunction "3_1-3") (pintype "passive"))
      (node (ref "JP4") (pin "4") (pinfunction "4_4") (pintype "passive"))
    )
    (net (code "23") (name "Net-(J1A-4)") (class "Default")
      (node (ref "J1") (pin "1-4") (pinfunction "4_1-4") (pintype "passive"))
      (node (ref "JP4") (pin "1") (pinfunction "1_1") (pintype "passive"))
    )
    (net (code "24") (name "Net-(J1A-5)") (class "Default")
      (node (ref "J1") (pin "1-5") (pinfunction "5_1-5") (pintype "passive"))
      (node (ref "JP4") (pin "5") (pinfunction "5_5") (pintype "passive"))
    )
    (net (code "25") (name "Net-(J1A-6)") (class "Default")
      (node (ref "J1") (pin "1-6") (pinfunction "6_1-6") (pintype "passive"))
      (node (ref "JP4") (pin "8") (pinfunction "8_8") (pintype "passive"))
    )
    (net (code "26") (name "Net-(J1B-3)") (class "Default")
      (node (ref "J1") (pin "2-3") (pinfunction "3_2-3") (pintype "passive"))
      (node (ref "JP3") (pin "4") (pinfunction "4_4") (pintype "passive"))
    )
    (net (code "27") (name "Net-(J1B-4)") (class "Default")
      (node (ref "J1") (pin "2-4") (pinfunction "4_2-4") (pintype "passive"))
      (node (ref "JP3") (pin "1") (pinfunction "1_1") (pintype "passive"))
    )
    (net (code "28") (name "Net-(J1B-5)") (class "Default")
      (node (ref "J1") (pin "2-5") (pinfunction "5_2-5") (pintype "passive"))
      (node (ref "JP3") (pin "5") (pinfunction "5_5") (pintype "passive"))
    )
    (net (code "29") (name "Net-(J1B-6)") (class "Default")
      (node (ref "J1") (pin "2-6") (pinfunction "6_2-6") (pintype "passive"))
      (node (ref "JP3") (pin "8") (pinfunction "8_8") (pintype "passive"))
    )
    (net (code "30") (name "Net-(LED1-PadA)") (class "Default")
      (node (ref "LED1") (pin "A") (pinfunction "A_A") (pintype "passive"))
      (node (ref "R43") (pin "1") (pinfunction "1_1") (pintype "passive"))
    )
    (net (code "31") (name "Net-(Q1-B)") (class "Default")
      (node (ref "Q1") (pin "1") (pinfunction "B_1") (pintype "passive"))
      (node (ref "Q2") (pin "3") (pinfunction "C_3") (pintype "passive"))
      (node (ref "R2") (pin "2") (pinfunction "2_2") (pintype "passive"))
      (node (ref "R3") (pin "2") (pinfunction "2_2") (pintype "passive"))
    )
    (net (code "32") (name "Net-(Q1-E)") (class "Default")
      (node (ref "Q1") (pin "2") (pinfunction "E_2") (pintype "passive"))
      (node (ref "Q2") (pin "1") (pinfunction "B_1") (pintype "passive"))
      (node (ref "R4") (pin "2") (pinfunction "2_2") (pintype "passive"))
    )
    (net (code "33") (name "Net-(Q3-B)") (class "Default")
      (node (ref "Q3") (pin "1") (pinfunction "B_1") (pintype "passive"))
      (node (ref "Q4") (pin "3") (pinfunction "C_3") (pintype "passive"))
      (node (ref "R37") (pin "2") (pinfunction "2_2") (pintype "passive"))
      (node (ref "R38") (pin "2") (pinfunction "2_2") (pintype "passive"))
    )
    (net (code "34") (name "Net-(Q3-E)") (class "Default")
      (node (ref "Q3") (pin "2") (pinfunction "E_2") (pintype "passive"))
      (node (ref "Q4") (pin "1") (pinfunction "B_1") (pintype "passive"))
      (node (ref "R39") (pin "2") (pinfunction "2_2") (pintype "passive"))
    )
    (net (code "35") (name "Net-(Q5-ADJ)") (class "Default")
      (node (ref "C21") (pin "2") (pinfunction "2_2") (pintype "passive"))
      (node (ref "Q5") (pin "1") (pinfunction "ADJ_1") (pintype "input"))
      (node (ref "R41") (pin "1") (pinfunction "1_1") (pintype "passive"))
    )
    (net (code "36") (name "Net-(Q5-OUT)") (class "Default")
      (node (ref "Q5") (pin "4") (pinfunction "OUT_4") (pintype "output"))
      (node (ref "R40") (pin "1") (pinfunction "1_1") (pintype "passive"))
    )
    (net (code "37") (name "Net-(R10-Pad1)") (class "Default")
      (node (ref "R10") (pin "1") (pinfunction "1_1") (pintype "passive"))
      (node (ref "R11") (pin "1") (pinfunction "1_1") (pintype "passive"))
      (node (ref "R12") (pin "2") (pinfunction "2_2") (pintype "passive"))
    )
    (net (code "38") (name "Net-(R26-Pad1)") (class "Default")
      (node (ref "R26") (pin "1") (pinfunction "1_1") (pintype "passive"))
      (node (ref "R27") (pin "1") (pinfunction "1_1") (pintype "passive"))
      (node (ref "R28") (pin "2") (pinfunction "2_2") (pintype "passive"))
    )
    (net (code "39") (name "Net-(TR1-1)") (class "Default")
      (node (ref "C6") (pin "1") (pinfunction "1_1") (pintype "passive"))
      (node (ref "JP3") (pin "7") (pinfunction "7_7") (pintype "passive"))
      (node (ref "R20") (pin "2") (pinfunction "2_2") (pintype "passive"))
      (node (ref "TR1") (pin "P$1") (pinfunction "1_P$1") (pintype "passive"))
    )
    (net (code "40") (name "Net-(TR1-4)") (class "Default")
      (node (ref "C6") (pin "2") (pinfunction "2_2") (pintype "passive"))
      (node (ref "JP3") (pin "3") (pinfunction "3_3") (pintype "passive"))
      (node (ref "R20") (pin "1") (pinfunction "1_1") (pintype "passive"))
      (node (ref "TR1") (pin "P$4") (pinfunction "4_P$4") (pintype "passive"))
    )
    (net (code "41") (name "Net-(TR1-5)") (class "Default")
      (node (ref "C5") (pin "1") (pinfunction "1_1") (pintype "passive"))
      (node (ref "JP3") (pin "6") (pinfunction "6_6") (pintype "passive"))
      (node (ref "R19") (pin "2") (pinfunction "2_2") (pintype "passive"))
      (node (ref "TR1") (pin "P$5") (pinfunction "5_P$5") (pintype "passive"))
    )
    (net (code "42") (name "Net-(TR1-8)") (class "Default")
      (node (ref "C5") (pin "2") (pinfunction "2_2") (pintype "passive"))
      (node (ref "JP3") (pin "2") (pinfunction "2_2") (pintype "passive"))
      (node (ref "R19") (pin "1") (pinfunction "1_1") (pintype "passive"))
      (node (ref "TR1") (pin "P$8") (pinfunction "8_P$8") (pintype "passive"))
    )
    (net (code "43") (name "Net-(TR1-10)") (class "Default")
      (node (ref "R7") (pin "1") (pinfunction "1_1") (pintype "passive"))
      (node (ref "TR1") (pin "P$10") (pinfunction "10_P$10") (pintype "passive"))
      (node (ref "TR1") (pin "P$11") (pinfunction "11_P$11") (pintype "passive"))
    )
    (net (code "44") (name "Net-(TR1-13)") (class "Default")
      (node (ref "R15") (pin "1") (pinfunction "1_1") (pintype "passive"))
      (node (ref "TR1") (pin "P$13") (pinfunction "13_P$13") (pintype "passive"))
    )
    (net (code "45") (name "Net-(TR1-14)") (class "Default")
      (node (ref "C4") (pin "2") (pinfunction "2_2") (pintype "passive"))
      (node (ref "R17") (pin "1") (pinfunction "1_1") (pintype "passive"))
      (node (ref "R18") (pin "1") (pinfunction "1_1") (pintype "passive"))
      (node (ref "TR1") (pin "P$14") (pinfunction "14_P$14") (pintype "passive"))
      (node (ref "TR1") (pin "P$15") (pinfunction "15_P$15") (pintype "passive"))
    )
    (net (code "46") (name "Net-(TR1-16)") (class "Default")
      (node (ref "R16") (pin "1") (pinfunction "1_1") (pintype "passive"))
      (node (ref "TR1") (pin "P$16") (pinfunction "16_P$16") (pintype "passive"))
    )
    (net (code "47") (name "Net-(TR2-1)") (class "Default")
      (node (ref "C12") (pin "1") (pinfunction "1_1") (pintype "passive"))
      (node (ref "JP4") (pin "7") (pinfunction "7_7") (pintype "passive"))
      (node (ref "R36") (pin "2") (pinfunction "2_2") (pintype "passive"))
      (node (ref "TR2") (pin "P$1") (pinfunction "1_P$1") (pintype "passive"))
    )
    (net (code "48") (name "Net-(TR2-4)") (class "Default")
      (node (ref "C12") (pin "2") (pinfunction "2_2") (pintype "passive"))
      (node (ref "JP4") (pin "3") (pinfunction "3_3") (pintype "passive"))
      (node (ref "R36") (pin "1") (pinfunction "1_1") (pintype "passive"))
      (node (ref "TR2") (pin "P$4") (pinfunction "4_P$4") (pintype "passive"))
    )
    (net (code "49") (name "Net-(TR2-5)") (class "Default")
      (node (ref "C11") (pin "1") (pinfunction "1_1") (pintype "passive"))
      (node (ref "JP4") (pin "6") (pinfunction "6_6") (pintype "passive"))
      (node (ref "R35") (pin "2") (pinfunction "2_2") (pintype "passive"))
      (node (ref "TR2") (pin "P$5") (pinfunction "5_P$5") (pintype "passive"))
    )
    (net (code "50") (name "Net-(TR2-8)") (class "Default")
      (node (ref "C11") (pin "2") (pinfunction "2_2") (pintype "passive"))
      (node (ref "JP4") (pin "2") (pinfunction "2_2") (pintype "passive"))
      (node (ref "R35") (pin "1") (pinfunction "1_1") (pintype "passive"))
      (node (ref "TR2") (pin "P$8") (pinfunction "8_P$8") (pintype "passive"))
    )
    (net (code "51") (name "Net-(TR2-10)") (class "Default")
      (node (ref "R23") (pin "1") (pinfunction "1_1") (pintype "passive"))
      (node (ref "TR2") (pin "P$10") (pinfunction "10_P$10") (pintype "passive"))
      (node (ref "TR2") (pin "P$11") (pinfunction "11_P$11") (pintype "passive"))
    )
    (net (code "52") (name "Net-(TR2-13)") (class "Default")
      (node (ref "R31") (pin "1") (pinfunction "1_1") (pintype "passive"))
      (node (ref "TR2") (pin "P$13") (pinfunction "13_P$13") (pintype "passive"))
    )
    (net (code "53") (name "Net-(TR2-14)") (class "Default")
      (node (ref "C10") (pin "2") (pinfunction "2_2") (pintype "passive"))
      (node (ref "R33") (pin "1") (pinfunction "1_1") (pintype "passive"))
      (node (ref "R34") (pin "1") (pinfunction "1_1") (pintype "passive"))
      (node (ref "TR2") (pin "P$14") (pinfunction "14_P$14") (pintype "passive"))
      (node (ref "TR2") (pin "P$15") (pinfunction "15_P$15") (pintype "passive"))
    )
    (net (code "54") (name "Net-(TR2-16)") (class "Default")
      (node (ref "R32") (pin "1") (pinfunction "1_1") (pintype "passive"))
      (node (ref "TR2") (pin "P$16") (pinfunction "16_P$16") (pintype "passive"))
    )
    (net (code "55") (name "Net-(U1A-CLK_OUT{slash}GPIO7)") (class "Default")
      (node (ref "R42") (pin "1") (pinfunction "1_1") (pintype "passive"))
      (node (ref "U1") (pin "33") (pinfunction "CLK_OUT/GPIO7_33") (pintype "bidirectional"))
    )
    (net (code "56") (name "Net-(U1E-ADJ)") (class "Default")
      (node (ref "R17") (pin "2") (pinfunction "2_2") (pintype "passive"))
      (node (ref "U1") (pin "54") (pinfunction "ADJ_54") (pintype "bidirectional"))
    )
    (net (code "57") (name "Net-(U1E-L_A{slash}GPIO)") (class "Default")
      (node (ref "R11") (pin "2") (pinfunction "2_2") (pintype "passive"))
      (node (ref "R8") (pin "2") (pinfunction "2_2") (pintype "passive"))
      (node (ref "U1") (pin "57") (pinfunction "L_A/GPIO_57") (pintype "bidirectional"))
    )
    (net (code "58") (name "Net-(U1E-L_B{slash}GPIO)") (class "Default")
      (node (ref "R10") (pin "2") (pinfunction "2_2") (pintype "passive"))
      (node (ref "R9") (pin "2") (pinfunction "2_2") (pintype "passive"))
      (node (ref "U1") (pin "56") (pinfunction "L_B/GPIO_56") (pintype "bidirectional"))
    )
    (net (code "59") (name "Net-(U1E-R_A{slash}GPIO)") (class "Default")
      (node (ref "C2") (pin "2") (pinfunction "2_2") (pintype "passive"))
      (node (ref "R13") (pin "2") (pinfunction "2_2") (pintype "passive"))
      (node (ref "R8") (pin "1") (pinfunction "1_1") (pintype "passive"))
      (node (ref "U1") (pin "58") (pinfunction "R_A/GPIO_58") (pintype "bidirectional"))
    )
    (net (code "60") (name "Net-(U1E-R_B{slash}GPIO)") (class "Default")
      (node (ref "C3") (pin "1") (pinfunction "1_1") (pintype "passive"))
      (node (ref "R14") (pin "2") (pinfunction "2_2") (pintype "passive"))
      (node (ref "R9") (pin "1") (pinfunction "1_1") (pintype "passive"))
      (node (ref "U1") (pin "55") (pinfunction "R_B/GPIO_55") (pintype "bidirectional"))
    )
    (net (code "61") (name "Net-(U1E-T_A{slash}GPIO)") (class "Default")
      (node (ref "R6") (pin "2") (pinfunction "2_2") (pintype "passive"))
      (node (ref "U1") (pin "51") (pinfunction "T_A/GPIO_51") (pintype "bidirectional"))
    )
    (net (code "62") (name "Net-(U1E-T_B{slash}GPIO)") (class "Default")
      (node (ref "R5") (pin "2") (pinfunction "2_2") (pintype "passive"))
      (node (ref "U1") (pin "50") (pinfunction "T_B/GPIO_50") (pintype "bidirectional"))
    )
    (net (code "63") (name "Net-(U1F-ADJ)") (class "Default")
      (node (ref "R33") (pin "2") (pinfunction "2_2") (pintype "passive"))
      (node (ref "U1") (pin "43") (pinfunction "ADJ_43") (pintype "bidirectional"))
    )
    (net (code "64") (name "Net-(U1F-L_A{slash}GPIO)") (class "Default")
      (node (ref "R24") (pin "2") (pinfunction "2_2") (pintype "passive"))
      (node (ref "R27") (pin "2") (pinfunction "2_2") (pintype "passive"))
      (node (ref "U1") (pin "40") (pinfunction "L_A/GPIO_40") (pintype "bidirectional"))
    )
    (net (code "65") (name "Net-(U1F-L_B{slash}GPIO)") (class "Default")
      (node (ref "R25") (pin "2") (pinfunction "2_2") (pintype "passive"))
      (node (ref "R26") (pin "2") (pinfunction "2_2") (pintype "passive"))
      (node (ref "U1") (pin "41") (pinfunction "L_B/GPIO_41") (pintype "bidirectional"))
    )
    (net (code "66") (name "Net-(U1F-R_A{slash}GPIO)") (class "Default")
      (node (ref "C8") (pin "2") (pinfunction "2_2") (pintype "passive"))
      (node (ref "R24") (pin "1") (pinfunction "1_1") (pintype "passive"))
      (node (ref "R29") (pin "2") (pinfunction "2_2") (pintype "passive"))
      (node (ref "U1") (pin "39") (pinfunction "R_A/GPIO_39") (pintype "bidirectional"))
    )
    (net (code "67") (name "Net-(U1F-R_B{slash}GPIO)") (class "Default")
      (node (ref "C9") (pin "1") (pinfunction "1_1") (pintype "passive"))
      (node (ref "R25") (pin "1") (pinfunction "1_1") (pintype "passive"))
      (node (ref "R30") (pin "2") (pinfunction "2_2") (pintype "passive"))
      (node (ref "U1") (pin "42") (pinfunction "R_B/GPIO_42") (pintype "bidirectional"))
    )
    (net (code "68") (name "Net-(U1F-T_A{slash}GPIO)") (class "Default")
      (node (ref "R22") (pin "2") (pinfunction "2_2") (pintype "passive"))
      (node (ref "U1") (pin "46") (pinfunction "T_A/GPIO_46") (pintype "bidirectional"))
    )
    (net (code "69") (name "Net-(U1F-T_B{slash}GPIO)") (class "Default")
      (node (ref "R21") (pin "2") (pinfunction "2_2") (pintype "passive"))
      (node (ref "U1") (pin "47") (pinfunction "T_B/GPIO_47") (pintype "bidirectional"))
    )
    (net (code "70") (name "PCM_2M_CLK") (class "Default")
      (node (ref "JP6") (pin "7") (pinfunction "7_7") (pintype "passive"))
      (node (ref "U1") (pin "18") (pinfunction "C2IO_18") (pintype "bidirectional"))
    )
    (net (code "71") (name "PCM_4M_CLK") (class "Default")
      (node (ref "JP6") (pin "10") (pinfunction "10_10") (pintype "passive"))
      (node (ref "U1") (pin "19") (pinfunction "C4IO_19") (pintype "bidirectional"))
    )
    (net (code "72") (name "PCM_ALT_FRAME") (class "Default")
      (node (ref "JP6") (pin "6") (pinfunction "6_6") (pintype "passive"))
      (node (ref "U1") (pin "28") (pinfunction "F1_0/GPIO2_28") (pintype "bidirectional"))
    )
    (net (code "73") (name "PCM_DATA_IO") (class "Default")
      (node (ref "JP6") (pin "11") (pinfunction "11_11") (pintype "passive"))
      (node (ref "U1") (pin "22") (pinfunction "STIO2/GPIO5_22") (pintype "bidirectional"))
    )
    (net (code "74") (name "PCM_DATA_OI") (class "Default")
      (node (ref "JP6") (pin "12") (pinfunction "12_12") (pintype "passive"))
      (node (ref "U1") (pin "21") (pinfunction "STIO1/GPIO4_21") (pintype "bidirectional"))
    )
    (net (code "75") (name "PCM_FRAME") (class "Default")
      (node (ref "JP6") (pin "9") (pinfunction "9_9") (pintype "passive"))
      (node (ref "U1") (pin "20") (pinfunction "F0IO_20") (pintype "bidirectional"))
    )
    (net (code "76") (name "SPI_CLK") (class "Default")
      (node (ref "U1") (pin "63") (pinfunction "~{IOR}_63") (pintype "input"))
      (node (ref "X1") (pin "9") (pinfunction "SCK_9") (pintype "passive"))
    )
    (net (code "77") (name "SPI_MISO") (class "Default")
      (node (ref "U1") (pin "4") (pinfunction "D7/SPI_TX_4") (pintype "bidirectional"))
      (node (ref "X1") (pin "7") (pinfunction "MISO_7") (pintype "passive"))
    )
    (net (code "78") (name "SPI_MOSI") (class "Default")
      (node (ref "U1") (pin "5") (pinfunction "D6/SPI_RX_5") (pintype "bidirectional"))
      (node (ref "X1") (pin "8") (pinfunction "MOSI_8") (pintype "passive"))
    )
    (net (code "79") (name "SYNC_I") (class "Default")
      (node (ref "JP6") (pin "8") (pinfunction "8_8") (pintype "passive"))
      (node (ref "U1") (pin "17") (pinfunction "SYNC_I_17") (pintype "bidirectional"))
    )
    (net (code "80") (name "SYNC_O") (class "Default")
      (node (ref "JP6") (pin "3") (pinfunction "3_3") (pintype "passive"))
      (node (ref "U1") (pin "16") (pinfunction "SYNC_O/GPIO6_16") (pintype "bidirectional"))
    )
    (net (code "81") (name "VCC") (class "Default")
      (node (ref "C13") (pin "2") (pinfunction "2_2") (pintype "passive"))
      (node (ref "C14") (pin "2") (pinfunction "2_2") (pintype "passive"))
      (node (ref "C15") (pin "2") (pinfunction "2_2") (pintype "passive"))
      (node (ref "C16") (pin "2") (pinfunction "2_2") (pintype "passive"))
      (node (ref "C17") (pin "2") (pinfunction "2_2") (pintype "passive"))
      (node (ref "C18") (pin "2") (pinfunction "2_2") (pintype "passive"))
      (node (ref "C19") (pin "2") (pinfunction "2_2") (pintype "passive"))
      (node (ref "C20") (pin "2") (pinfunction "2_2") (pintype "passive"))
      (node (ref "C23") (pin "1") (pinfunction "1_1") (pintype "passive"))
      (node (ref "D1") (pin "3") (pinfunction "M_3") (pintype "passive"))
      (node (ref "D10") (pin "3") (pinfunction "M_3") (pintype "passive"))
      (node (ref "D2") (pin "2") (pinfunction "C_2") (pintype "passive"))
      (node (ref "D3") (pin "2") (pinfunction "C_2") (pintype "passive"))
      (node (ref "D4") (pin "2") (pinfunction "C_2") (pintype "passive"))
      (node (ref "D5") (pin "2") (pinfunction "C_2") (pintype "passive"))
      (node (ref "D6") (pin "2") (pinfunction "C_2") (pintype "passive"))
      (node (ref "D7") (pin "2") (pinfunction "C_2") (pintype "passive"))
      (node (ref "D8") (pin "2") (pinfunction "C_2") (pintype "passive"))
      (node (ref "D9") (pin "2") (pinfunction "C_2") (pintype "passive"))
      (node (ref "JP6") (pin "1") (pinfunction "1_1") (pintype "passive"))
      (node (ref "Q1") (pin "3") (pinfunction "C_3") (pintype "passive"))
      (node (ref "Q3") (pin "3") (pinfunction "C_3") (pintype "passive"))
      (node (ref "Q5") (pin "2") (pinfunction "EN_2") (pintype "input"))
      (node (ref "Q5") (pin "5") (pinfunction "EN_5") (pintype "input"))
      (node (ref "Q5") (pin "6") (pinfunction "VDD_6") (pintype "power_in"))
      (node (ref "R1") (pin "2") (pinfunction "2_2") (pintype "passive"))
      (node (ref "R12") (pin "1") (pinfunction "1_1") (pintype "passive"))
      (node (ref "R18") (pin "2") (pinfunction "2_2") (pintype "passive"))
      (node (ref "R2") (pin "1") (pinfunction "1_1") (pintype "passive"))
      (node (ref "R28") (pin "1") (pinfunction "1_1") (pintype "passive"))
      (node (ref "R34") (pin "2") (pinfunction "2_2") (pintype "passive"))
      (node (ref "R37") (pin "1") (pinfunction "1_1") (pintype "passive"))
      (node (ref "R43") (pin "2") (pinfunction "2_2") (pintype "passive"))
      (node (ref "U1") (pin "13") (pinfunction "VDD_13") (pintype "passive"))
      (node (ref "U1") (pin "24") (pinfunction "VDD_24") (pintype "passive"))
      (node (ref "U1") (pin "29") (pinfunction "VDD_29") (pintype "passive"))
      (node (ref "U1") (pin "37") (pinfunction "VDD_37") (pintype "passive"))
      (node (ref "U1") (pin "44") (pinfunction "VDD_44") (pintype "passive"))
      (node (ref "U1") (pin "53") (pinfunction "VDD_53") (pintype "passive"))
      (node (ref "U1") (pin "60") (pinfunction "VDD_60") (pintype "passive"))
      (node (ref "X1") (pin "1") (pinfunction "3V3_1") (pintype "passive"))
    )
    (net (code "82") (name "VCXO_OUT") (class "Default")
      (node (ref "R40") (pin "2") (pinfunction "2_2") (pintype "passive"))
      (node (ref "U1") (pin "30") (pinfunction "OSC_IN_30") (pintype "input"))
    )
    (net (code "83") (name "VCXO_VCTRL") (class "Default")
      (node (ref "C22") (pin "2") (pinfunction "2_2") (pintype "passive"))
      (node (ref "JP5") (pin "1") (pinfunction "1_1") (pintype "passive"))
      (node (ref "R41") (pin "2") (pinfunction "2_2") (pintype "passive"))
    )
    (net (code "84") (name "unconnected-(D1-A-Pad1)") (class "Default")
      (node (ref "D1") (pin "1") (pinfunction "A_1") (pintype "passive"))
    )
    (net (code "85") (name "unconnected-(D10-A-Pad1)") (class "Default")
      (node (ref "D10") (pin "1") (pinfunction "A_1") (pintype "passive"))
    )
    (net (code "86") (name "unconnected-(J1A-1-Pad1-1)") (class "Default")
      (node (ref "J1") (pin "1-1") (pinfunction "1_1-1") (pintype "passive"))
    )
    (net (code "87") (name "unconnected-(J1A-2-Pad1-2)") (class "Default")
      (node (ref "J1") (pin "1-2") (pinfunction "2_1-2") (pintype "passive"))
    )
    (net (code "88") (name "unconnected-(J1A-7-Pad1-7)") (class "Default")
      (node (ref "J1") (pin "1-7") (pinfunction "7_1-7") (pintype "passive"))
    )
    (net (code "89") (name "unconnected-(J1A-8-Pad1-8)") (class "Default")
      (node (ref "J1") (pin "1-8") (pinfunction "8_1-8") (pintype "passive"))
    )
    (net (code "90") (name "unconnected-(J1B-1-Pad2-1)") (class "Default")
      (node (ref "J1") (pin "2-1") (pinfunction "1_2-1") (pintype "passive"))
    )
    (net (code "91") (name "unconnected-(J1B-2-Pad2-2)") (class "Default")
      (node (ref "J1") (pin "2-2") (pinfunction "2_2-2") (pintype "passive"))
    )
    (net (code "92") (name "unconnected-(J1B-7-Pad2-7)") (class "Default")
      (node (ref "J1") (pin "2-7") (pinfunction "7_2-7") (pintype "passive"))
    )
    (net (code "93") (name "unconnected-(J1B-8-Pad2-8)") (class "Default")
      (node (ref "J1") (pin "2-8") (pinfunction "8_2-8") (pintype "passive"))
    )
    (net (code "94") (name "unconnected-(JP6-Pad4)") (class "Default")
      (node (ref "JP6") (pin "4") (pinfunction "4_4") (pintype "passive"))
    )
    (net (code "95") (name "unconnected-(U1A-OSC_OUT-Pad31)") (class "Default")
      (node (ref "U1") (pin "31") (pinfunction "OSC_OUT_31") (pintype "output"))
    )
    (net (code "96") (name "unconnected-(U1D-~{WAIT}-Pad61)") (class "Default")
      (node (ref "U1") (pin "61") (pinfunction "~{WAIT}_61") (pintype "input"))
    )
    (net (code "97") (name "unconnected-(X1-SCL-Pad5)") (class "Default")
      (node (ref "X1") (pin "5") (pinfunction "SCL_5") (pintype "passive"))
    )
    (net (code "98") (name "unconnected-(X1-SDA-Pad6)") (class "Default")
      (node (ref "X1") (pin "6") (pinfunction "SDA_6") (pintype "passive"))
    )
    (net (code "99") (name "~{INT}") (class "Default")
      (node (ref "R1") (pin "1") (pinfunction "1_1") (pintype "passive"))
      (node (ref "U1") (pin "14") (pinfunction "~{INT}_14") (pintype "output"))
      (node (ref "X1") (pin "4") (pinfunction "RXD_4") (pintype "passive"))
    )
    (net (code "100") (name "~{RES}") (class "Default")
      (node (ref "U1") (pin "15") (pinfunction "~{RES}_15") (pintype "input"))
      (node (ref "X1") (pin "3") (pinfunction "TXD_3") (pintype "passive"))
    )
    (net (code "101") (name "~{SPI_SEL}") (class "Default")
      (node (ref "U1") (pin "1") (pinfunction "~{CS/SPISEL}_1") (pintype "input"))
      (node (ref "X1") (pin "10") (pinfunction "SSEL_10") (pintype "passive"))
    )
  )
)
